# SCH_ACC_Register_2021-10-14.net
KiCad netlist of a schematic drawn in EasyEDA
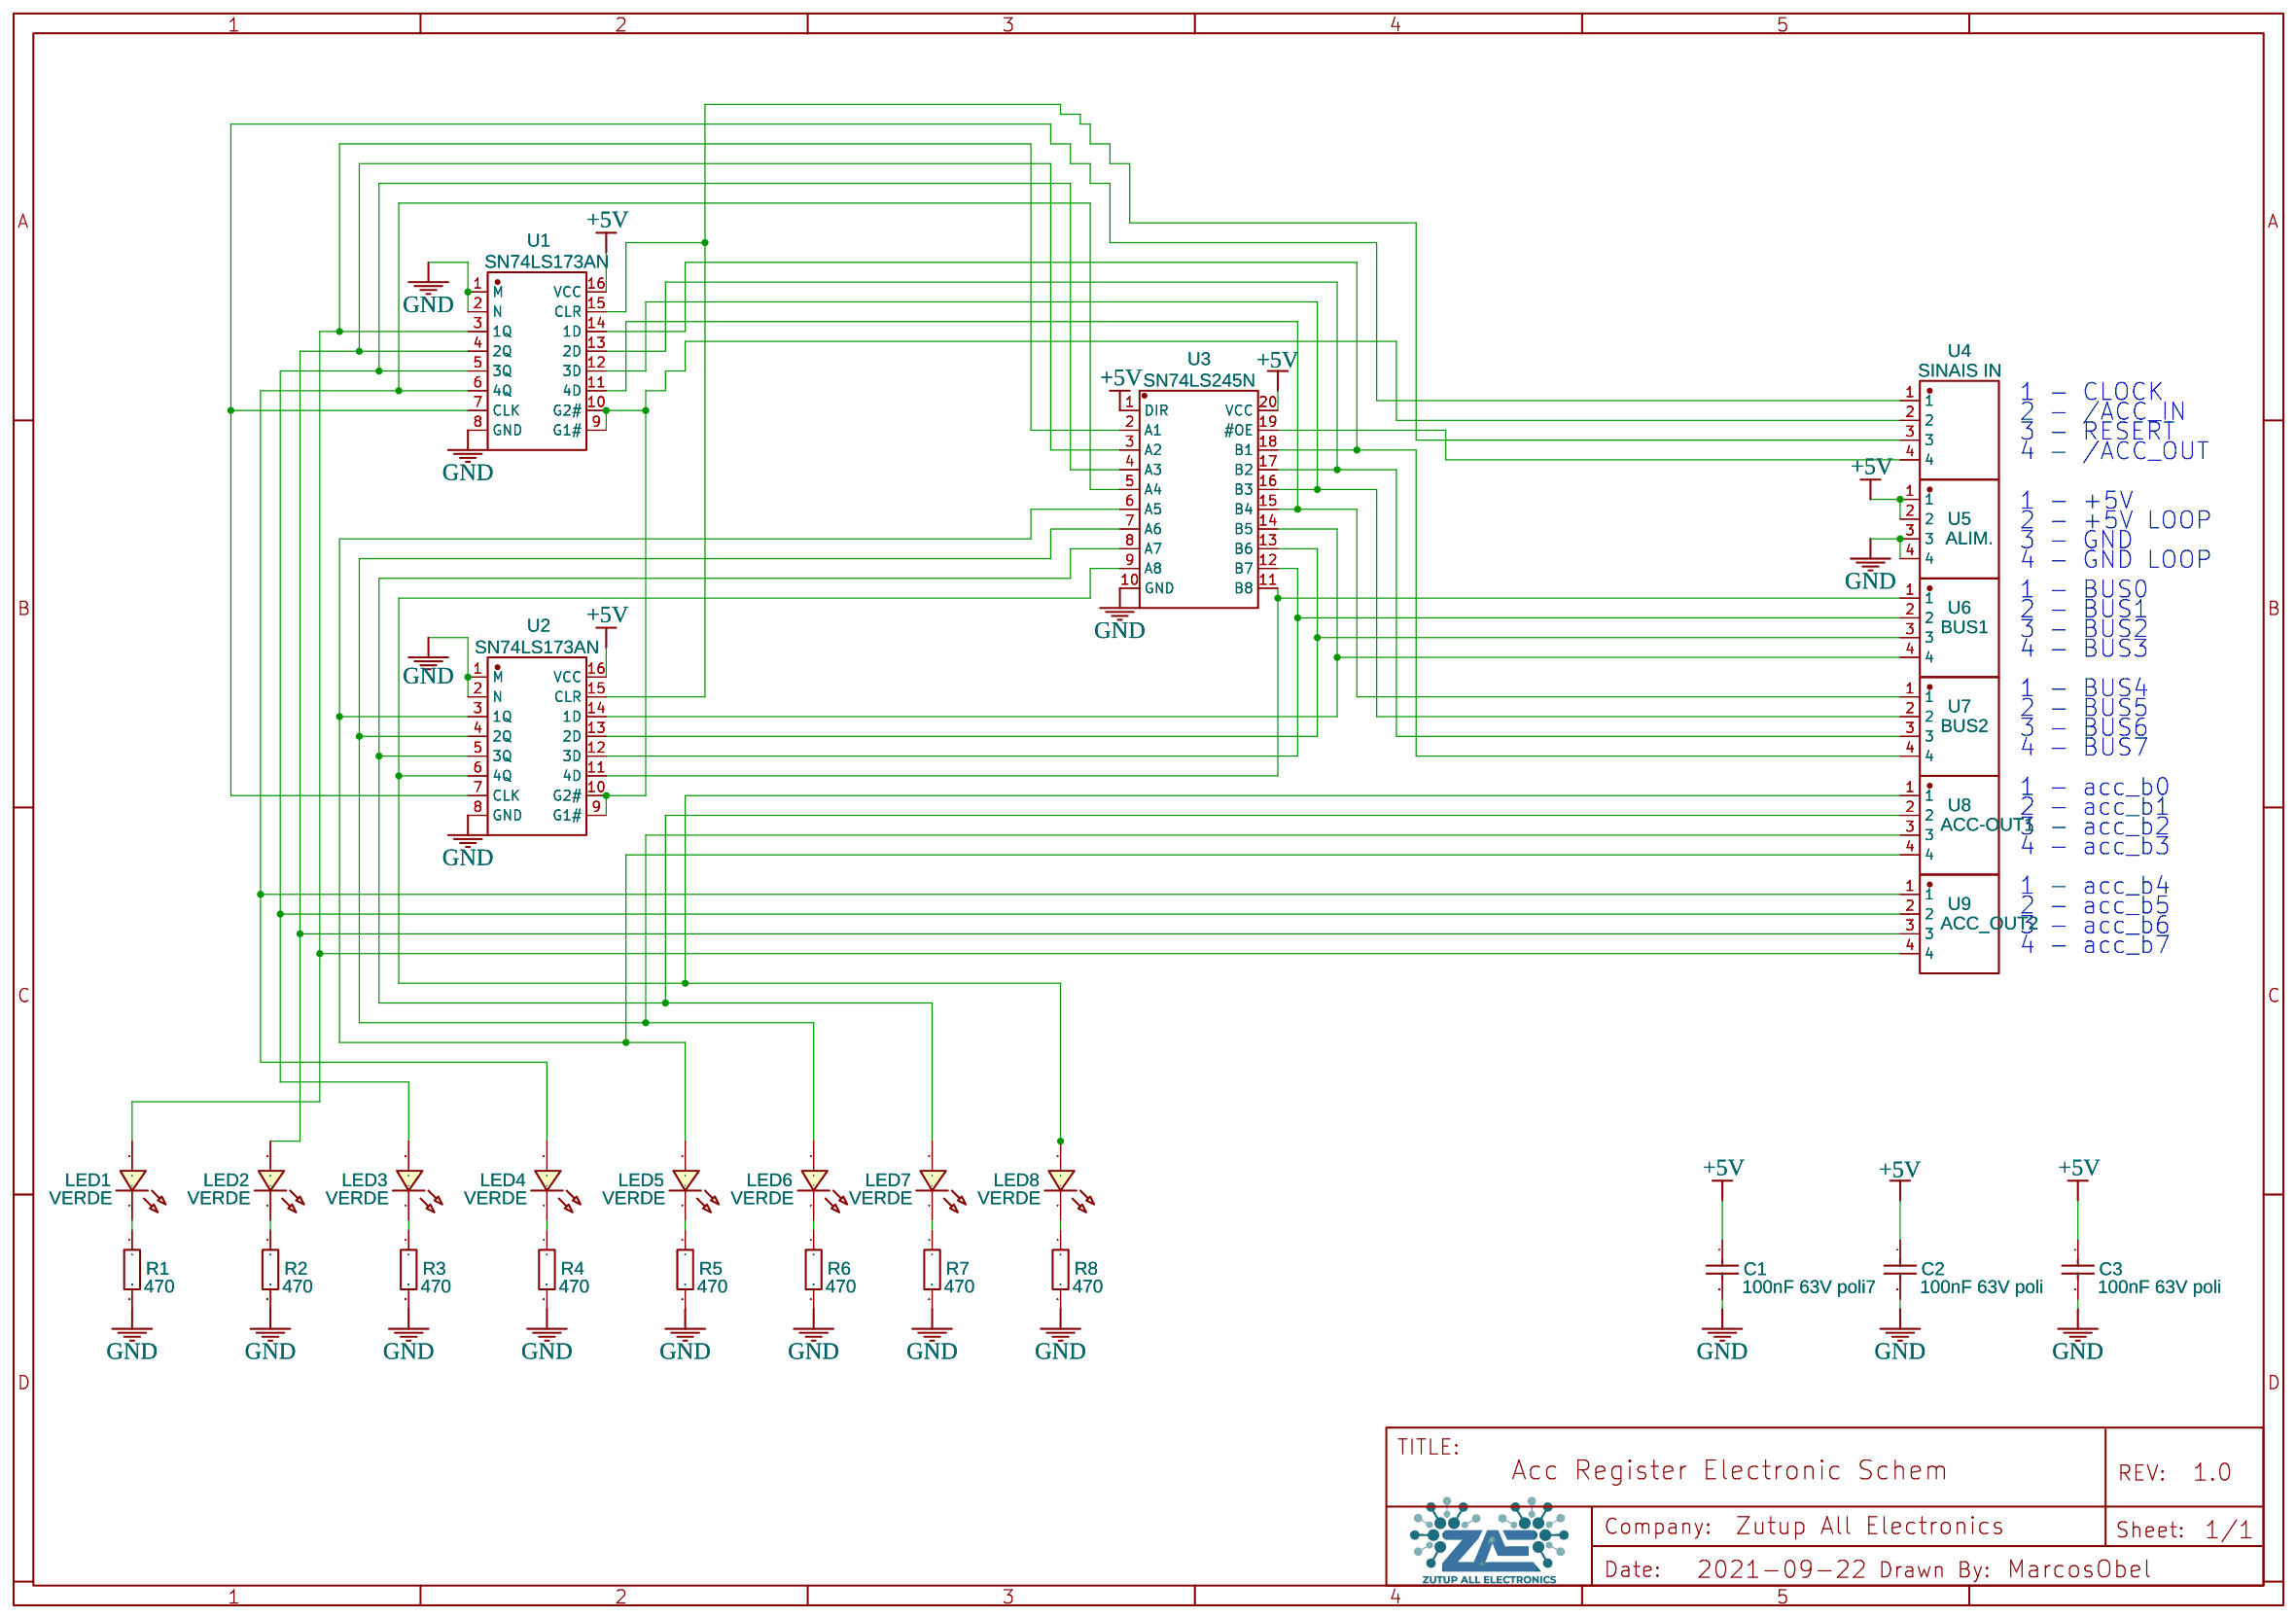
[diagram p0: schematic sheet]

(export (version "E")
  (design (tool "Eeschema 10.0.6"))
  (components
    (comp (ref "C1")
      (value "100nF 63V poli7")
      (fields
        (field (name "BOM_Manufacturer Part") "SR305C105KAR")
        (field (name "BOM_Supplier Part") "C444741")
      )
      (libsource (lib "") (part "SR305C105KAR"))
    )
    (comp (ref "C2")
      (value "100nF 63V poli")
      (fields
        (field (name "BOM_Manufacturer Part") "SR305C105KAR")
        (field (name "BOM_Supplier Part") "C444741")
      )
      (libsource (lib "") (part "SR305C105KAR"))
    )
    (comp (ref "C3")
      (value "100nF 63V poli")
      (fields
        (field (name "BOM_Manufacturer Part") "SR305C105KAR")
        (field (name "BOM_Supplier Part") "C444741")
      )
      (libsource (lib "") (part "SR305C105KAR"))
    )
    (comp (ref "LED1")
      (value "VERDE")
      (fields (field (name "BOM_Manufacturer Part") "264-7GD") (field (name "BOM_Supplier Part") "C605465"))
      (libsource (lib "") (part "264-7GD"))
    )
    (comp (ref "LED2")
      (value "VERDE")
      (fields (field (name "BOM_Manufacturer Part") "264-7GD") (field (name "BOM_Supplier Part") "C605465"))
      (libsource (lib "") (part "264-7GD"))
    )
    (comp (ref "LED3")
      (value "VERDE")
      (fields (field (name "BOM_Manufacturer Part") "264-7GD") (field (name "BOM_Supplier Part") "C605465"))
      (libsource (lib "") (part "264-7GD"))
    )
    (comp (ref "LED4")
      (value "VERDE")
      (fields (field (name "BOM_Manufacturer Part") "264-7GD") (field (name "BOM_Supplier Part") "C605465"))
      (libsource (lib "") (part "264-7GD"))
    )
    (comp (ref "LED5")
      (value "VERDE")
      (fields (field (name "BOM_Manufacturer Part") "264-7GD") (field (name "BOM_Supplier Part") "C605465"))
      (libsource (lib "") (part "264-7GD"))
    )
    (comp (ref "LED6")
      (value "VERDE")
      (fields (field (name "BOM_Manufacturer Part") "264-7GD") (field (name "BOM_Supplier Part") "C605465"))
      (libsource (lib "") (part "264-7GD"))
    )
    (comp (ref "LED7")
      (value "VERDE")
      (fields (field (name "BOM_Manufacturer Part") "264-7GD") (field (name "BOM_Supplier Part") "C605465"))
      (libsource (lib "") (part "264-7GD"))
    )
    (comp (ref "LED8")
      (value "VERDE")
      (fields (field (name "BOM_Manufacturer Part") "264-7GD") (field (name "BOM_Supplier Part") "C605465"))
      (libsource (lib "") (part "264-7GD"))
    )
    (comp (ref "R1")
      (value "470")
      (fields
        (field (name "BOM_Manufacturer Part") "CFR02SJ0823A10")
        (field (name "BOM_Supplier Part") "C69876")
      )
      (libsource (lib "") (part "CFR02SJ0823A10"))
    )
    (comp (ref "R2")
      (value "470")
      (fields
        (field (name "BOM_Manufacturer Part") "CFR02SJ0823A10")
        (field (name "BOM_Supplier Part") "C69876")
      )
      (libsource (lib "") (part "CFR02SJ0823A10"))
    )
    (comp (ref "R3")
      (value "470")
      (fields
        (field (name "BOM_Manufacturer Part") "CFR02SJ0823A10")
        (field (name "BOM_Supplier Part") "C69876")
      )
      (libsource (lib "") (part "CFR02SJ0823A10"))
    )
    (comp (ref "R4")
      (value "470")
      (fields
        (field (name "BOM_Manufacturer Part") "CFR02SJ0823A10")
        (field (name "BOM_Supplier Part") "C69876")
      )
      (libsource (lib "") (part "CFR02SJ0823A10"))
    )
    (comp (ref "R5")
      (value "470")
      (fields
        (field (name "BOM_Manufacturer Part") "CFR02SJ0823A10")
        (field (name "BOM_Supplier Part") "C69876")
      )
      (libsource (lib "") (part "CFR02SJ0823A10"))
    )
    (comp (ref "R6")
      (value "470")
      (fields
        (field (name "BOM_Manufacturer Part") "CFR02SJ0823A10")
        (field (name "BOM_Supplier Part") "C69876")
      )
      (libsource (lib "") (part "CFR02SJ0823A10"))
    )
    (comp (ref "R7")
      (value "470")
      (fields
        (field (name "BOM_Manufacturer Part") "CFR02SJ0823A10")
        (field (name "BOM_Supplier Part") "C69876")
      )
      (libsource (lib "") (part "CFR02SJ0823A10"))
    )
    (comp (ref "R8")
      (value "470")
      (fields
        (field (name "BOM_Manufacturer Part") "CFR02SJ0823A10")
        (field (name "BOM_Supplier Part") "C69876")
      )
      (libsource (lib "") (part "CFR02SJ0823A10"))
    )
    (comp (ref "U1")
      (value "SN74LS173AN")
      (fields (field (name "BOM_Supplier Part") "C1550125"))
      (libsource (lib "") (part "SN74LS173AN"))
    )
    (comp (ref "U2")
      (value "SN74LS173AN")
      (fields (field (name "BOM_Supplier Part") "C1550125"))
      (libsource (lib "") (part "SN74LS173AN"))
    )
    (comp (ref "U3")
      (value "SN74LS245N")
      (fields (field (name "BOM_Supplier Part") "C352966"))
      (libsource (lib "") (part "SN74LS245N"))
    )
    (comp (ref "U4")
      (value "SINAIS IN")
      (fields (field (name "BOM_Manufacturer Part") "171825-4") (field (name "BOM_Supplier Part") "C210162"))
      (libsource (lib "") (part "171825-4"))
    )
    (comp (ref "U5")
      (value "ALIM.")
      (fields (field (name "BOM_Manufacturer Part") "171825-4") (field (name "BOM_Supplier Part") "C210162"))
      (libsource (lib "") (part "171825-4"))
    )
    (comp (ref "U6")
      (value "BUS1")
      (fields (field (name "BOM_Manufacturer Part") "171825-4") (field (name "BOM_Supplier Part") "C210162"))
      (libsource (lib "") (part "171825-4"))
    )
    (comp (ref "U7")
      (value "BUS2")
      (fields (field (name "BOM_Manufacturer Part") "171825-4") (field (name "BOM_Supplier Part") "C210162"))
      (libsource (lib "") (part "171825-4"))
    )
    (comp (ref "U8")
      (value "ACC-OUT1")
      (fields (field (name "BOM_Manufacturer Part") "171825-4") (field (name "BOM_Supplier Part") "C210162"))
      (libsource (lib "") (part "171825-4"))
    )
    (comp (ref "U9")
      (value "ACC_OUT2")
      (fields (field (name "BOM_Manufacturer Part") "171825-4") (field (name "BOM_Supplier Part") "C210162"))
      (libsource (lib "") (part "171825-4"))
    )
  )
  (nets
    (net (code "1") (name "+5V") (class "Default")
      (node (ref "C1") (pin "1") (pinfunction "1_1") (pintype "input"))
      (node (ref "C2") (pin "1") (pinfunction "1_1") (pintype "input"))
      (node (ref "C3") (pin "1") (pinfunction "1_1") (pintype "input"))
      (node (ref "U1") (pin "16") (pinfunction "VCC_16") (pintype "unspecified"))
      (node (ref "U2") (pin "16") (pinfunction "VCC_16") (pintype "unspecified"))
      (node (ref "U3") (pin "1") (pinfunction "DIR_1") (pintype "unspecified"))
      (node (ref "U3") (pin "20") (pinfunction "VCC_20") (pintype "unspecified"))
      (node (ref "U5") (pin "1") (pinfunction "1_1") (pintype "unspecified"))
      (node (ref "U5") (pin "2") (pinfunction "2_2") (pintype "unspecified"))
    )
    (net (code "2") (name "GND") (class "Default")
      (node (ref "C1") (pin "2") (pinfunction "2_2") (pintype "input"))
      (node (ref "C2") (pin "2") (pinfunction "2_2") (pintype "input"))
      (node (ref "C3") (pin "2") (pinfunction "2_2") (pintype "input"))
      (node (ref "R1") (pin "2") (pinfunction "2_2") (pintype "input"))
      (node (ref "R2") (pin "2") (pinfunction "2_2") (pintype "input"))
      (node (ref "R3") (pin "2") (pinfunction "2_2") (pintype "input"))
      (node (ref "R4") (pin "2") (pinfunction "2_2") (pintype "input"))
      (node (ref "R5") (pin "2") (pinfunction "2_2") (pintype "input"))
      (node (ref "R6") (pin "2") (pinfunction "2_2") (pintype "input"))
      (node (ref "R7") (pin "2") (pinfunction "2_2") (pintype "input"))
      (node (ref "R8") (pin "2") (pinfunction "2_2") (pintype "input"))
      (node (ref "U1") (pin "1") (pinfunction "M_1") (pintype "unspecified"))
      (node (ref "U1") (pin "2") (pinfunction "N_2") (pintype "unspecified"))
      (node (ref "U1") (pin "8") (pinfunction "GND_8") (pintype "unspecified"))
      (node (ref "U2") (pin "1") (pinfunction "M_1") (pintype "unspecified"))
      (node (ref "U2") (pin "2") (pinfunction "N_2") (pintype "unspecified"))
      (node (ref "U2") (pin "8") (pinfunction "GND_8") (pintype "unspecified"))
      (node (ref "U3") (pin "10") (pinfunction "GND_10") (pintype "unspecified"))
      (node (ref "U5") (pin "3") (pinfunction "3_3") (pintype "unspecified"))
      (node (ref "U5") (pin "4") (pinfunction "4_4") (pintype "unspecified"))
    )
    (net (code "3") (name "Net-(LED1-+)") (class "Default")
      (node (ref "LED1") (pin "2") (pinfunction "+_2") (pintype "unspecified"))
      (node (ref "U1") (pin "3") (pinfunction "1Q_3") (pintype "unspecified"))
      (node (ref "U3") (pin "2") (pinfunction "A1_2") (pintype "unspecified"))
      (node (ref "U9") (pin "4") (pinfunction "4_4") (pintype "unspecified"))
    )
    (net (code "4") (name "Net-(LED1--)") (class "Default")
      (node (ref "LED1") (pin "1") (pinfunction "-_1") (pintype "unspecified"))
      (node (ref "R1") (pin "1") (pinfunction "1_1") (pintype "input"))
    )
    (net (code "5") (name "Net-(LED2-+)") (class "Default")
      (node (ref "LED2") (pin "2") (pinfunction "+_2") (pintype "unspecified"))
      (node (ref "U1") (pin "4") (pinfunction "2Q_4") (pintype "unspecified"))
      (node (ref "U3") (pin "3") (pinfunction "A2_3") (pintype "unspecified"))
      (node (ref "U9") (pin "3") (pinfunction "3_3") (pintype "unspecified"))
    )
    (net (code "6") (name "Net-(LED2--)") (class "Default")
      (node (ref "LED2") (pin "1") (pinfunction "-_1") (pintype "unspecified"))
      (node (ref "R2") (pin "1") (pinfunction "1_1") (pintype "input"))
    )
    (net (code "7") (name "Net-(LED3-+)") (class "Default")
      (node (ref "LED3") (pin "2") (pinfunction "+_2") (pintype "unspecified"))
      (node (ref "U1") (pin "5") (pinfunction "3Q_5") (pintype "unspecified"))
      (node (ref "U3") (pin "4") (pinfunction "A3_4") (pintype "unspecified"))
      (node (ref "U9") (pin "2") (pinfunction "2_2") (pintype "unspecified"))
    )
    (net (code "8") (name "Net-(LED3--)") (class "Default")
      (node (ref "LED3") (pin "1") (pinfunction "-_1") (pintype "unspecified"))
      (node (ref "R3") (pin "1") (pinfunction "1_1") (pintype "input"))
    )
    (net (code "9") (name "Net-(LED4-+)") (class "Default")
      (node (ref "LED4") (pin "2") (pinfunction "+_2") (pintype "unspecified"))
      (node (ref "U1") (pin "6") (pinfunction "4Q_6") (pintype "unspecified"))
      (node (ref "U3") (pin "5") (pinfunction "A4_5") (pintype "unspecified"))
      (node (ref "U9") (pin "1") (pinfunction "1_1") (pintype "unspecified"))
    )
    (net (code "10") (name "Net-(LED4--)") (class "Default")
      (node (ref "LED4") (pin "1") (pinfunction "-_1") (pintype "unspecified"))
      (node (ref "R4") (pin "1") (pinfunction "1_1") (pintype "input"))
    )
    (net (code "11") (name "Net-(LED5-+)") (class "Default")
      (node (ref "LED5") (pin "2") (pinfunction "+_2") (pintype "unspecified"))
      (node (ref "U2") (pin "3") (pinfunction "1Q_3") (pintype "unspecified"))
      (node (ref "U3") (pin "6") (pinfunction "A5_6") (pintype "unspecified"))
      (node (ref "U8") (pin "4") (pinfunction "4_4") (pintype "unspecified"))
    )
    (net (code "12") (name "Net-(LED5--)") (class "Default")
      (node (ref "LED5") (pin "1") (pinfunction "-_1") (pintype "unspecified"))
      (node (ref "R5") (pin "1") (pinfunction "1_1") (pintype "input"))
    )
    (net (code "13") (name "Net-(LED6-+)") (class "Default")
      (node (ref "LED6") (pin "2") (pinfunction "+_2") (pintype "unspecified"))
      (node (ref "U2") (pin "4") (pinfunction "2Q_4") (pintype "unspecified"))
      (node (ref "U3") (pin "7") (pinfunction "A6_7") (pintype "unspecified"))
      (node (ref "U8") (pin "3") (pinfunction "3_3") (pintype "unspecified"))
    )
    (net (code "14") (name "Net-(LED6--)") (class "Default")
      (node (ref "LED6") (pin "1") (pinfunction "-_1") (pintype "unspecified"))
      (node (ref "R6") (pin "1") (pinfunction "1_1") (pintype "input"))
    )
    (net (code "15") (name "Net-(LED7-+)") (class "Default")
      (node (ref "LED7") (pin "2") (pinfunction "+_2") (pintype "unspecified"))
      (node (ref "U2") (pin "5") (pinfunction "3Q_5") (pintype "unspecified"))
      (node (ref "U3") (pin "8") (pinfunction "A7_8") (pintype "unspecified"))
      (node (ref "U8") (pin "2") (pinfunction "2_2") (pintype "unspecified"))
    )
    (net (code "16") (name "Net-(LED7--)") (class "Default")
      (node (ref "LED7") (pin "1") (pinfunction "-_1") (pintype "unspecified"))
      (node (ref "R7") (pin "1") (pinfunction "1_1") (pintype "input"))
    )
    (net (code "17") (name "Net-(LED8-+)") (class "Default")
      (node (ref "LED8") (pin "2") (pinfunction "+_2") (pintype "unspecified"))
      (node (ref "U2") (pin "6") (pinfunction "4Q_6") (pintype "unspecified"))
      (node (ref "U3") (pin "9") (pinfunction "A8_9") (pintype "unspecified"))
      (node (ref "U8") (pin "1") (pinfunction "1_1") (pintype "unspecified"))
    )
    (net (code "18") (name "Net-(LED8--)") (class "Default")
      (node (ref "LED8") (pin "1") (pinfunction "-_1") (pintype "unspecified"))
      (node (ref "R8") (pin "1") (pinfunction "1_1") (pintype "input"))
    )
    (net (code "19") (name "Net-(U1-1D)") (class "Default")
      (node (ref "U1") (pin "14") (pinfunction "1D_14") (pintype "unspecified"))
      (node (ref "U3") (pin "18") (pinfunction "B1_18") (pintype "unspecified"))
      (node (ref "U7") (pin "4") (pinfunction "4_4") (pintype "unspecified"))
    )
    (net (code "20") (name "Net-(U1-2D)") (class "Default")
      (node (ref "U1") (pin "13") (pinfunction "2D_13") (pintype "unspecified"))
      (node (ref "U3") (pin "17") (pinfunction "B2_17") (pintype "unspecified"))
      (node (ref "U7") (pin "3") (pinfunction "3_3") (pintype "unspecified"))
    )
    (net (code "21") (name "Net-(U1-3D)") (class "Default")
      (node (ref "U1") (pin "12") (pinfunction "3D_12") (pintype "unspecified"))
      (node (ref "U3") (pin "16") (pinfunction "B3_16") (pintype "unspecified"))
      (node (ref "U7") (pin "2") (pinfunction "2_2") (pintype "unspecified"))
    )
    (net (code "22") (name "Net-(U1-4D)") (class "Default")
      (node (ref "U1") (pin "11") (pinfunction "4D_11") (pintype "unspecified"))
      (node (ref "U3") (pin "15") (pinfunction "B4_15") (pintype "unspecified"))
      (node (ref "U7") (pin "1") (pinfunction "1_1") (pintype "unspecified"))
    )
    (net (code "23") (name "Net-(U1-CLK)") (class "Default")
      (node (ref "U1") (pin "7") (pinfunction "CLK_7") (pintype "unspecified"))
      (node (ref "U2") (pin "7") (pinfunction "CLK_7") (pintype "unspecified"))
      (node (ref "U4") (pin "1") (pinfunction "1_1") (pintype "unspecified"))
    )
    (net (code "24") (name "Net-(U1-CLR)") (class "Default")
      (node (ref "U1") (pin "15") (pinfunction "CLR_15") (pintype "unspecified"))
      (node (ref "U2") (pin "15") (pinfunction "CLR_15") (pintype "unspecified"))
      (node (ref "U4") (pin "3") (pinfunction "3_3") (pintype "unspecified"))
    )
    (net (code "25") (name "Net-(U1-G1#)") (class "Default")
      (node (ref "U1") (pin "10") (pinfunction "G2#_10") (pintype "unspecified"))
      (node (ref "U1") (pin "9") (pinfunction "G1#_9") (pintype "unspecified"))
      (node (ref "U2") (pin "10") (pinfunction "G2#_10") (pintype "unspecified"))
      (node (ref "U2") (pin "9") (pinfunction "G1#_9") (pintype "unspecified"))
      (node (ref "U4") (pin "2") (pinfunction "2_2") (pintype "unspecified"))
    )
    (net (code "26") (name "Net-(U2-1D)") (class "Default")
      (node (ref "U2") (pin "14") (pinfunction "1D_14") (pintype "unspecified"))
      (node (ref "U3") (pin "14") (pinfunction "B5_14") (pintype "unspecified"))
      (node (ref "U6") (pin "4") (pinfunction "4_4") (pintype "unspecified"))
    )
    (net (code "27") (name "Net-(U2-2D)") (class "Default")
      (node (ref "U2") (pin "13") (pinfunction "2D_13") (pintype "unspecified"))
      (node (ref "U3") (pin "13") (pinfunction "B6_13") (pintype "unspecified"))
      (node (ref "U6") (pin "3") (pinfunction "3_3") (pintype "unspecified"))
    )
    (net (code "28") (name "Net-(U2-3D)") (class "Default")
      (node (ref "U2") (pin "12") (pinfunction "3D_12") (pintype "unspecified"))
      (node (ref "U3") (pin "12") (pinfunction "B7_12") (pintype "unspecified"))
      (node (ref "U6") (pin "2") (pinfunction "2_2") (pintype "unspecified"))
    )
    (net (code "29") (name "Net-(U2-4D)") (class "Default")
      (node (ref "U2") (pin "11") (pinfunction "4D_11") (pintype "unspecified"))
      (node (ref "U3") (pin "11") (pinfunction "B8_11") (pintype "unspecified"))
      (node (ref "U6") (pin "1") (pinfunction "1_1") (pintype "unspecified"))
    )
    (net (code "30") (name "Net-(U3-#OE)") (class "Default")
      (node (ref "U3") (pin "19") (pinfunction "#OE_19") (pintype "unspecified"))
      (node (ref "U4") (pin "4") (pinfunction "4_4") (pintype "unspecified"))
    )
  )
)
